# PLT-01-RevA.net
KiCad netlist of a schematic drawn in EAGLE
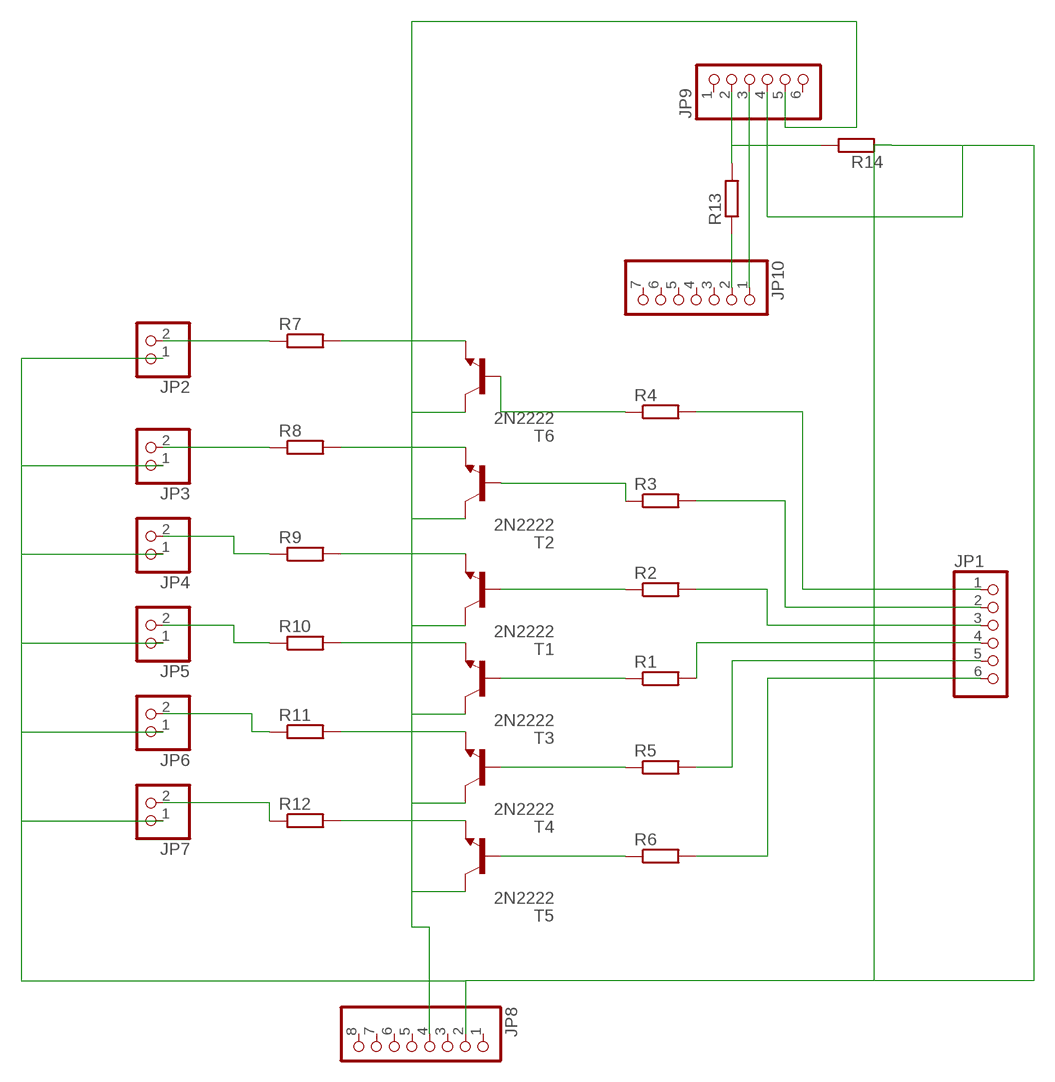
[diagram p0: schematic, sheet 1]

(export (version "E")
  (design (tool "Eeschema 10.0.6"))
  (components
    (comp (ref "JP1")
      (value "PINHD-1X6")
      (footprint "eagle-import:1X06")
      (libsource (lib "eagle-import") (part "PINHD-1X6"))
    )
    (comp (ref "JP2")
      (value "PINHD-1X2")
      (footprint "eagle-import:1X02")
      (libsource (lib "eagle-import") (part "PINHD-1X2"))
    )
    (comp (ref "JP3")
      (value "PINHD-1X2")
      (footprint "eagle-import:1X02")
      (libsource (lib "eagle-import") (part "PINHD-1X2"))
    )
    (comp (ref "JP4")
      (value "PINHD-1X2")
      (footprint "eagle-import:1X02")
      (libsource (lib "eagle-import") (part "PINHD-1X2"))
    )
    (comp (ref "JP5")
      (value "PINHD-1X2")
      (footprint "eagle-import:1X02")
      (libsource (lib "eagle-import") (part "PINHD-1X2"))
    )
    (comp (ref "JP6")
      (value "PINHD-1X2")
      (footprint "eagle-import:1X02")
      (libsource (lib "eagle-import") (part "PINHD-1X2"))
    )
    (comp (ref "JP7")
      (value "PINHD-1X2")
      (footprint "eagle-import:1X02")
      (libsource (lib "eagle-import") (part "PINHD-1X2"))
    )
    (comp (ref "JP8")
      (value "PINHD-1X8")
      (footprint "eagle-import:1X08")
      (libsource (lib "eagle-import") (part "PINHD-1X8"))
    )
    (comp (ref "JP9")
      (value "PINHD-1X6")
      (footprint "eagle-import:1X06")
      (libsource (lib "eagle-import") (part "PINHD-1X6"))
    )
    (comp (ref "JP10")
      (value "PINHD-1X7")
      (footprint "eagle-import:1X07")
      (libsource (lib "eagle-import") (part "PINHD-1X7"))
    )
    (comp (ref "R1")
      (value "R-EU_0207/10")
      (footprint "eagle-import:0207_10")
      (libsource (lib "eagle-import") (part "R-EU_0207/10"))
    )
    (comp (ref "R2")
      (value "R-EU_0207/10")
      (footprint "eagle-import:0207_10")
      (libsource (lib "eagle-import") (part "R-EU_0207/10"))
    )
    (comp (ref "R3")
      (value "R-EU_0207/10")
      (footprint "eagle-import:0207_10")
      (libsource (lib "eagle-import") (part "R-EU_0207/10"))
    )
    (comp (ref "R4")
      (value "R-EU_0207/10")
      (footprint "eagle-import:0207_10")
      (libsource (lib "eagle-import") (part "R-EU_0207/10"))
    )
    (comp (ref "R5")
      (value "R-EU_0207/10")
      (footprint "eagle-import:0207_10")
      (libsource (lib "eagle-import") (part "R-EU_0207/10"))
    )
    (comp (ref "R6")
      (value "R-EU_0207/10")
      (footprint "eagle-import:0207_10")
      (libsource (lib "eagle-import") (part "R-EU_0207/10"))
    )
    (comp (ref "R7")
      (value "R-EU_0207/10")
      (footprint "eagle-import:0207_10")
      (libsource (lib "eagle-import") (part "R-EU_0207/10"))
    )
    (comp (ref "R8")
      (value "R-EU_0207/10")
      (footprint "eagle-import:0207_10")
      (libsource (lib "eagle-import") (part "R-EU_0207/10"))
    )
    (comp (ref "R9")
      (value "R-EU_0207/10")
      (footprint "eagle-import:0207_10")
      (libsource (lib "eagle-import") (part "R-EU_0207/10"))
    )
    (comp (ref "R10")
      (value "R-EU_0207/10")
      (footprint "eagle-import:0207_10")
      (libsource (lib "eagle-import") (part "R-EU_0207/10"))
    )
    (comp (ref "R11")
      (value "R-EU_0207/10")
      (footprint "eagle-import:0207_10")
      (libsource (lib "eagle-import") (part "R-EU_0207/10"))
    )
    (comp (ref "R12")
      (value "R-EU_0207/10")
      (footprint "eagle-import:0207_10")
      (libsource (lib "eagle-import") (part "R-EU_0207/10"))
    )
    (comp (ref "R13")
      (value "R-EU_0207/10")
      (footprint "eagle-import:0207_10")
      (libsource (lib "eagle-import") (part "R-EU_0207/10"))
    )
    (comp (ref "R14")
      (value "R-EU_0207/10")
      (footprint "eagle-import:0207_10")
      (libsource (lib "eagle-import") (part "R-EU_0207/10"))
    )
    (comp (ref "T1")
      (value "2N2222")
      (footprint "eagle-import:TO18")
      (libsource (lib "eagle-import") (part "2N2222"))
    )
    (comp (ref "T2")
      (value "2N2222")
      (footprint "eagle-import:TO18")
      (libsource (lib "eagle-import") (part "2N2222"))
    )
    (comp (ref "T3")
      (value "2N2222")
      (footprint "eagle-import:TO18")
      (libsource (lib "eagle-import") (part "2N2222"))
    )
    (comp (ref "T4")
      (value "2N2222")
      (footprint "eagle-import:TO18")
      (libsource (lib "eagle-import") (part "2N2222"))
    )
    (comp (ref "T5")
      (value "2N2222")
      (footprint "eagle-import:TO18")
      (libsource (lib "eagle-import") (part "2N2222"))
    )
    (comp (ref "T6")
      (value "2N2222")
      (footprint "eagle-import:TO18")
      (libsource (lib "eagle-import") (part "2N2222"))
    )
  )
  (nets
    (net (code "1") (name "Net-(JP1-Pad1)") (class "Default")
      (node (ref "JP1") (pin "1") (pinfunction "1_1") (pintype "passive"))
      (node (ref "R4") (pin "2") (pinfunction "2_2") (pintype "passive"))
    )
    (net (code "2") (name "Net-(JP1-Pad2)") (class "Default")
      (node (ref "JP1") (pin "2") (pinfunction "2_2") (pintype "passive"))
      (node (ref "R3") (pin "2") (pinfunction "2_2") (pintype "passive"))
    )
    (net (code "3") (name "Net-(JP1-Pad3)") (class "Default")
      (node (ref "JP1") (pin "3") (pinfunction "3_3") (pintype "passive"))
      (node (ref "R2") (pin "2") (pinfunction "2_2") (pintype "passive"))
    )
    (net (code "4") (name "Net-(JP1-Pad4)") (class "Default")
      (node (ref "JP1") (pin "4") (pinfunction "4_4") (pintype "passive"))
      (node (ref "R1") (pin "2") (pinfunction "2_2") (pintype "passive"))
    )
    (net (code "5") (name "Net-(JP1-Pad5)") (class "Default")
      (node (ref "JP1") (pin "5") (pinfunction "5_5") (pintype "passive"))
      (node (ref "R5") (pin "2") (pinfunction "2_2") (pintype "passive"))
    )
    (net (code "6") (name "Net-(JP1-Pad6)") (class "Default")
      (node (ref "JP1") (pin "6") (pinfunction "6_6") (pintype "passive"))
      (node (ref "R6") (pin "2") (pinfunction "2_2") (pintype "passive"))
    )
    (net (code "7") (name "Net-(JP2-Pad1)") (class "Default")
      (node (ref "JP2") (pin "1") (pinfunction "1_1") (pintype "passive"))
      (node (ref "JP3") (pin "1") (pinfunction "1_1") (pintype "passive"))
      (node (ref "JP4") (pin "1") (pinfunction "1_1") (pintype "passive"))
      (node (ref "JP5") (pin "1") (pinfunction "1_1") (pintype "passive"))
      (node (ref "JP6") (pin "1") (pinfunction "1_1") (pintype "passive"))
      (node (ref "JP8") (pin "2") (pinfunction "2_2") (pintype "passive"))
      (node (ref "JP9") (pin "4") (pinfunction "4_4") (pintype "passive"))
      (node (ref "R14") (pin "1") (pinfunction "1_1") (pintype "passive"))
    )
    (net (code "8") (name "Net-(JP2-Pad2)") (class "Default")
      (node (ref "JP2") (pin "2") (pinfunction "2_2") (pintype "passive"))
      (node (ref "R7") (pin "1") (pinfunction "1_1") (pintype "passive"))
    )
    (net (code "9") (name "Net-(JP3-Pad2)") (class "Default")
      (node (ref "JP3") (pin "2") (pinfunction "2_2") (pintype "passive"))
      (node (ref "R8") (pin "1") (pinfunction "1_1") (pintype "passive"))
    )
    (net (code "10") (name "Net-(JP4-Pad2)") (class "Default")
      (node (ref "JP4") (pin "2") (pinfunction "2_2") (pintype "passive"))
      (node (ref "R9") (pin "1") (pinfunction "1_1") (pintype "passive"))
    )
    (net (code "11") (name "Net-(JP5-Pad2)") (class "Default")
      (node (ref "JP5") (pin "2") (pinfunction "2_2") (pintype "passive"))
      (node (ref "R10") (pin "1") (pinfunction "1_1") (pintype "passive"))
    )
    (net (code "12") (name "Net-(JP6-Pad2)") (class "Default")
      (node (ref "JP6") (pin "2") (pinfunction "2_2") (pintype "passive"))
      (node (ref "R11") (pin "1") (pinfunction "1_1") (pintype "passive"))
    )
    (net (code "13") (name "Net-(JP7-Pad2)") (class "Default")
      (node (ref "JP7") (pin "2") (pinfunction "2_2") (pintype "passive"))
      (node (ref "R12") (pin "1") (pinfunction "1_1") (pintype "passive"))
    )
    (net (code "14") (name "Net-(JP9-Pad2)") (class "Default")
      (node (ref "JP9") (pin "2") (pinfunction "2_2") (pintype "passive"))
      (node (ref "R13") (pin "2") (pinfunction "2_2") (pintype "passive"))
      (node (ref "R14") (pin "2") (pinfunction "2_2") (pintype "passive"))
    )
    (net (code "15") (name "Net-(JP10-Pad1)") (class "Default")
      (node (ref "JP10") (pin "1") (pinfunction "1_1") (pintype "passive"))
      (node (ref "JP9") (pin "3") (pinfunction "3_3") (pintype "passive"))
    )
    (net (code "16") (name "Net-(JP10-Pad2)") (class "Default")
      (node (ref "JP10") (pin "2") (pinfunction "2_2") (pintype "passive"))
      (node (ref "R13") (pin "1") (pinfunction "1_1") (pintype "passive"))
    )
    (net (code "17") (name "Net-(T1-B)") (class "Default")
      (node (ref "R2") (pin "1") (pinfunction "1_1") (pintype "passive"))
      (node (ref "T1") (pin "2") (pinfunction "B_2") (pintype "passive"))
    )
    (net (code "18") (name "Net-(T1-C)") (class "Default")
      (node (ref "JP8") (pin "4") (pinfunction "4_4") (pintype "passive"))
      (node (ref "JP9") (pin "5") (pinfunction "5_5") (pintype "passive"))
      (node (ref "T1") (pin "3") (pinfunction "C_3") (pintype "passive"))
      (node (ref "T2") (pin "3") (pinfunction "C_3") (pintype "passive"))
      (node (ref "T3") (pin "3") (pinfunction "C_3") (pintype "passive"))
      (node (ref "T4") (pin "3") (pinfunction "C_3") (pintype "passive"))
      (node (ref "T5") (pin "3") (pinfunction "C_3") (pintype "passive"))
      (node (ref "T6") (pin "3") (pinfunction "C_3") (pintype "passive"))
    )
    (net (code "19") (name "Net-(T1-E)") (class "Default")
      (node (ref "R9") (pin "2") (pinfunction "2_2") (pintype "passive"))
      (node (ref "T1") (pin "1") (pinfunction "E_1") (pintype "passive"))
    )
    (net (code "20") (name "Net-(T2-B)") (class "Default")
      (node (ref "R3") (pin "1") (pinfunction "1_1") (pintype "passive"))
      (node (ref "T2") (pin "2") (pinfunction "B_2") (pintype "passive"))
    )
    (net (code "21") (name "Net-(T2-E)") (class "Default")
      (node (ref "R8") (pin "2") (pinfunction "2_2") (pintype "passive"))
      (node (ref "T2") (pin "1") (pinfunction "E_1") (pintype "passive"))
    )
    (net (code "22") (name "Net-(T3-B)") (class "Default")
      (node (ref "R1") (pin "1") (pinfunction "1_1") (pintype "passive"))
      (node (ref "T3") (pin "2") (pinfunction "B_2") (pintype "passive"))
    )
    (net (code "23") (name "Net-(T3-E)") (class "Default")
      (node (ref "R10") (pin "2") (pinfunction "2_2") (pintype "passive"))
      (node (ref "T3") (pin "1") (pinfunction "E_1") (pintype "passive"))
    )
    (net (code "24") (name "Net-(T4-B)") (class "Default")
      (node (ref "R5") (pin "1") (pinfunction "1_1") (pintype "passive"))
      (node (ref "T4") (pin "2") (pinfunction "B_2") (pintype "passive"))
    )
    (net (code "25") (name "Net-(T4-E)") (class "Default")
      (node (ref "R11") (pin "2") (pinfunction "2_2") (pintype "passive"))
      (node (ref "T4") (pin "1") (pinfunction "E_1") (pintype "passive"))
    )
    (net (code "26") (name "Net-(T5-B)") (class "Default")
      (node (ref "R6") (pin "1") (pinfunction "1_1") (pintype "passive"))
      (node (ref "T5") (pin "2") (pinfunction "B_2") (pintype "passive"))
    )
    (net (code "27") (name "Net-(T5-E)") (class "Default")
      (node (ref "R12") (pin "2") (pinfunction "2_2") (pintype "passive"))
      (node (ref "T5") (pin "1") (pinfunction "E_1") (pintype "passive"))
    )
    (net (code "28") (name "Net-(T6-B)") (class "Default")
      (node (ref "R4") (pin "1") (pinfunction "1_1") (pintype "passive"))
      (node (ref "T6") (pin "2") (pinfunction "B_2") (pintype "passive"))
    )
    (net (code "29") (name "Net-(T6-E)") (class "Default")
      (node (ref "R7") (pin "2") (pinfunction "2_2") (pintype "passive"))
      (node (ref "T6") (pin "1") (pinfunction "E_1") (pintype "passive"))
    )
    (net (code "30") (name "unconnected-(JP7-Pad1)") (class "Default")
      (node (ref "JP7") (pin "1") (pinfunction "1_1") (pintype "passive"))
    )
    (net (code "31") (name "unconnected-(JP8-Pad1)") (class "Default")
      (node (ref "JP8") (pin "1") (pinfunction "1_1") (pintype "passive"))
    )
    (net (code "32") (name "unconnected-(JP8-Pad3)") (class "Default")
      (node (ref "JP8") (pin "3") (pinfunction "3_3") (pintype "passive"))
    )
    (net (code "33") (name "unconnected-(JP8-Pad5)") (class "Default")
      (node (ref "JP8") (pin "5") (pinfunction "5_5") (pintype "passive"))
    )
    (net (code "34") (name "unconnected-(JP8-Pad6)") (class "Default")
      (node (ref "JP8") (pin "6") (pinfunction "6_6") (pintype "passive"))
    )
    (net (code "35") (name "unconnected-(JP8-Pad7)") (class "Default")
      (node (ref "JP8") (pin "7") (pinfunction "7_7") (pintype "passive"))
    )
    (net (code "36") (name "unconnected-(JP8-Pad8)") (class "Default")
      (node (ref "JP8") (pin "8") (pinfunction "8_8") (pintype "passive"))
    )
    (net (code "37") (name "unconnected-(JP9-Pad1)") (class "Default")
      (node (ref "JP9") (pin "1") (pinfunction "1_1") (pintype "passive"))
    )
    (net (code "38") (name "unconnected-(JP9-Pad6)") (class "Default")
      (node (ref "JP9") (pin "6") (pinfunction "6_6") (pintype "passive"))
    )
    (net (code "39") (name "unconnected-(JP10-Pad3)") (class "Default")
      (node (ref "JP10") (pin "3") (pinfunction "3_3") (pintype "passive"))
    )
    (net (code "40") (name "unconnected-(JP10-Pad4)") (class "Default")
      (node (ref "JP10") (pin "4") (pinfunction "4_4") (pintype "passive"))
    )
    (net (code "41") (name "unconnected-(JP10-Pad5)") (class "Default")
      (node (ref "JP10") (pin "5") (pinfunction "5_5") (pintype "passive"))
    )
    (net (code "42") (name "unconnected-(JP10-Pad6)") (class "Default")
      (node (ref "JP10") (pin "6") (pinfunction "6_6") (pintype "passive"))
    )
    (net (code "43") (name "unconnected-(JP10-Pad7)") (class "Default")
      (node (ref "JP10") (pin "7") (pinfunction "7_7") (pintype "passive"))
    )
  )
)
